# main.net
KiCad netlist of a schematic drawn in Altium Designer
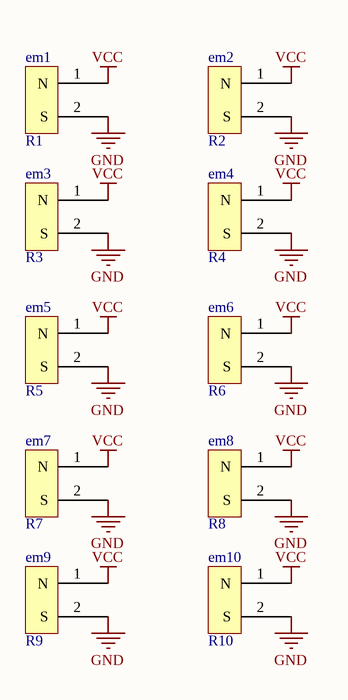
[diagram p0: main.SchDoc]

(export (version "E")
  (design (tool "Eeschema 10.0.6"))
  (components
    (comp (ref "em1")
      (value "R1")
      (footprint "electromagnet")
      (libsource (lib "Integrated_Library") (part "electromagnet"))
    )
    (comp (ref "em2")
      (value "R2")
      (footprint "electromagnet")
      (libsource (lib "Integrated_Library") (part "electromagnet"))
    )
    (comp (ref "em3")
      (value "R3")
      (footprint "electromagnet")
      (libsource (lib "Integrated_Library") (part "electromagnet"))
    )
    (comp (ref "em4")
      (value "R4")
      (footprint "electromagnet")
      (libsource (lib "Integrated_Library") (part "electromagnet"))
    )
    (comp (ref "em5")
      (value "R5")
      (footprint "electromagnet")
      (libsource (lib "Integrated_Library") (part "electromagnet"))
    )
    (comp (ref "em6")
      (value "R6")
      (footprint "electromagnet")
      (libsource (lib "Integrated_Library") (part "electromagnet"))
    )
    (comp (ref "em7")
      (value "R7")
      (footprint "electromagnet")
      (libsource (lib "Integrated_Library") (part "electromagnet"))
    )
    (comp (ref "em8")
      (value "R8")
      (footprint "electromagnet")
      (libsource (lib "Integrated_Library") (part "electromagnet"))
    )
    (comp (ref "em9")
      (value "R9")
      (footprint "electromagnet")
      (libsource (lib "Integrated_Library") (part "electromagnet"))
    )
    (comp (ref "em10")
      (value "R10")
      (footprint "electromagnet")
      (libsource (lib "Integrated_Library") (part "electromagnet"))
    )
  )
  (nets
    (net (code "1") (name "GND") (class "Default")
      (node (ref "em1") (pin "2") (pinfunction "S_2") (pintype "passive"))
      (node (ref "em10") (pin "2") (pinfunction "S_2") (pintype "passive"))
      (node (ref "em2") (pin "2") (pinfunction "S_2") (pintype "passive"))
      (node (ref "em3") (pin "2") (pinfunction "S_2") (pintype "passive"))
      (node (ref "em4") (pin "2") (pinfunction "S_2") (pintype "passive"))
      (node (ref "em5") (pin "2") (pinfunction "S_2") (pintype "passive"))
      (node (ref "em6") (pin "2") (pinfunction "S_2") (pintype "passive"))
      (node (ref "em7") (pin "2") (pinfunction "S_2") (pintype "passive"))
      (node (ref "em8") (pin "2") (pinfunction "S_2") (pintype "passive"))
      (node (ref "em9") (pin "2") (pinfunction "S_2") (pintype "passive"))
    )
    (net (code "2") (name "VCC") (class "Default")
      (node (ref "em1") (pin "1") (pinfunction "N_1") (pintype "passive"))
      (node (ref "em10") (pin "1") (pinfunction "N_1") (pintype "passive"))
      (node (ref "em2") (pin "1") (pinfunction "N_1") (pintype "passive"))
      (node (ref "em3") (pin "1") (pinfunction "N_1") (pintype "passive"))
      (node (ref "em4") (pin "1") (pinfunction "N_1") (pintype "passive"))
      (node (ref "em5") (pin "1") (pinfunction "N_1") (pintype "passive"))
      (node (ref "em6") (pin "1") (pinfunction "N_1") (pintype "passive"))
      (node (ref "em7") (pin "1") (pinfunction "N_1") (pintype "passive"))
      (node (ref "em8") (pin "1") (pinfunction "N_1") (pintype "passive"))
      (node (ref "em9") (pin "1") (pinfunction "N_1") (pintype "passive"))
    )
  )
)
